# reverse_protection.net
KiCad netlist of a schematic drawn in Altium Designer
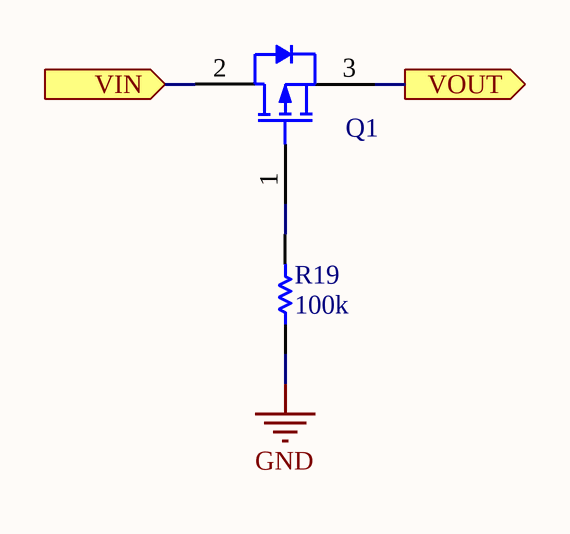
[diagram p0: reverse_protection.SchDoc]

(export (version "E")
  (design (tool "Eeschema 10.0.6"))
  (components
    (comp (ref "Q1")
      (value "Infineon IPD90P04P405ATMA1")
      (footprint "PCB-n8uhnm53xyssvg7v0f21-1")
      (description "Single P-Channel 40 V 4.7 mOhm 118 nC OptiMOS Power Mosfet - TO-252-3")
      (fields (field (name "MANUFACTURER PART NUMBER") "IPD90P04P405ATMA1"))
      (libsource (lib "CommunityVault") (part "CMP-b5fa7db8f8eb6a3d-1"))
    )
    (comp (ref "R19")
      (value "100k")
      (footprint "RESC1609X50X30LL10T20")
      (description "RES SMD 100K OHM 1% 1/10W 0603")
      (libsource (lib "CommunityVault") (part "CMP-16231689-4"))
    )
  )
  (nets
    (net (code "1") (name "/VIN") (class "Default")
      (node (ref "Q1") (pin "2") (pinfunction "D_2") (pintype "passive"))
    )
    (net (code "2") (name "/VOUT") (class "Default")
      (node (ref "Q1") (pin "3") (pinfunction "S_3") (pintype "passive"))
    )
    (net (code "3") (name "GND") (class "Default")
      (node (ref "R19") (pin "1") (pinfunction "1_1") (pintype "passive"))
    )
    (net (code "4") (name "Net-(Q1-G)") (class "Default")
      (node (ref "Q1") (pin "1") (pinfunction "G_1") (pintype "passive"))
      (node (ref "R19") (pin "2") (pinfunction "2_2") (pintype "passive"))
    )
  )
)
